# Lora.net
KiCad netlist of a schematic drawn in Altium Designer
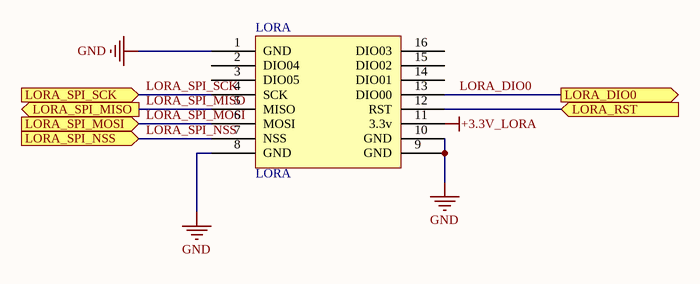
[diagram p0: Lora.SchDoc]

(export (version "E")
  (design (tool "Eeschema 10.0.6"))
  (components
    (comp (ref "LORA") (value "LORA") (footprint "LORA-RA2-SMD") (libsource (lib "AfraLIB") (part "LORA")))
  )
  (nets
    (net (code "1") (name "+3.3V_LORA") (class "Default")
      (node (ref "LORA") (pin "11") (pinfunction "3.3v_11") (pintype "passive"))
    )
    (net (code "2") (name "/LORA_DIO0") (class "Default")
      (node (ref "LORA") (pin "13") (pinfunction "DIO00_13") (pintype "passive"))
    )
    (net (code "3") (name "/LORA_RST") (class "Default")
      (node (ref "LORA") (pin "12") (pinfunction "RST_12") (pintype "passive"))
    )
    (net (code "4") (name "/LORA_SPI_MISO") (class "Default")
      (node (ref "LORA") (pin "5") (pinfunction "MISO_5") (pintype "passive"))
    )
    (net (code "5") (name "/LORA_SPI_MOSI") (class "Default")
      (node (ref "LORA") (pin "6") (pinfunction "MOSI_6") (pintype "passive"))
    )
    (net (code "6") (name "/LORA_SPI_NSS") (class "Default")
      (node (ref "LORA") (pin "7") (pinfunction "NSS_7") (pintype "passive"))
    )
    (net (code "7") (name "/LORA_SPI_SCK") (class "Default")
      (node (ref "LORA") (pin "4") (pinfunction "SCK_4") (pintype "passive"))
    )
    (net (code "8") (name "GND") (class "Default")
      (node (ref "LORA") (pin "1") (pinfunction "GND_1") (pintype "passive"))
      (node (ref "LORA") (pin "10") (pinfunction "GND_10") (pintype "passive"))
      (node (ref "LORA") (pin "8") (pinfunction "GND_8") (pintype "passive"))
      (node (ref "LORA") (pin "9") (pinfunction "GND_9") (pintype "passive"))
    )
    (net (code "9") (name "unconnected-(LORA-DIO01-Pad14)") (class "Default")
      (node (ref "LORA") (pin "14") (pinfunction "DIO01_14") (pintype "passive"))
    )
    (net (code "10") (name "unconnected-(LORA-DIO02-Pad15)") (class "Default")
      (node (ref "LORA") (pin "15") (pinfunction "DIO02_15") (pintype "passive"))
    )
    (net (code "11") (name "unconnected-(LORA-DIO03-Pad16)") (class "Default")
      (node (ref "LORA") (pin "16") (pinfunction "DIO03_16") (pintype "passive"))
    )
    (net (code "12") (name "unconnected-(LORA-DIO04-Pad2)") (class "Default")
      (node (ref "LORA") (pin "2") (pinfunction "DIO04_2") (pintype "passive"))
    )
    (net (code "13") (name "unconnected-(LORA-DIO05-Pad3)") (class "Default")
      (node (ref "LORA") (pin "3") (pinfunction "DIO05_3") (pintype "passive"))
    )
  )
)
